# ReboostV2__Isense.net
KiCad netlist of a schematic drawn in Altium Designer
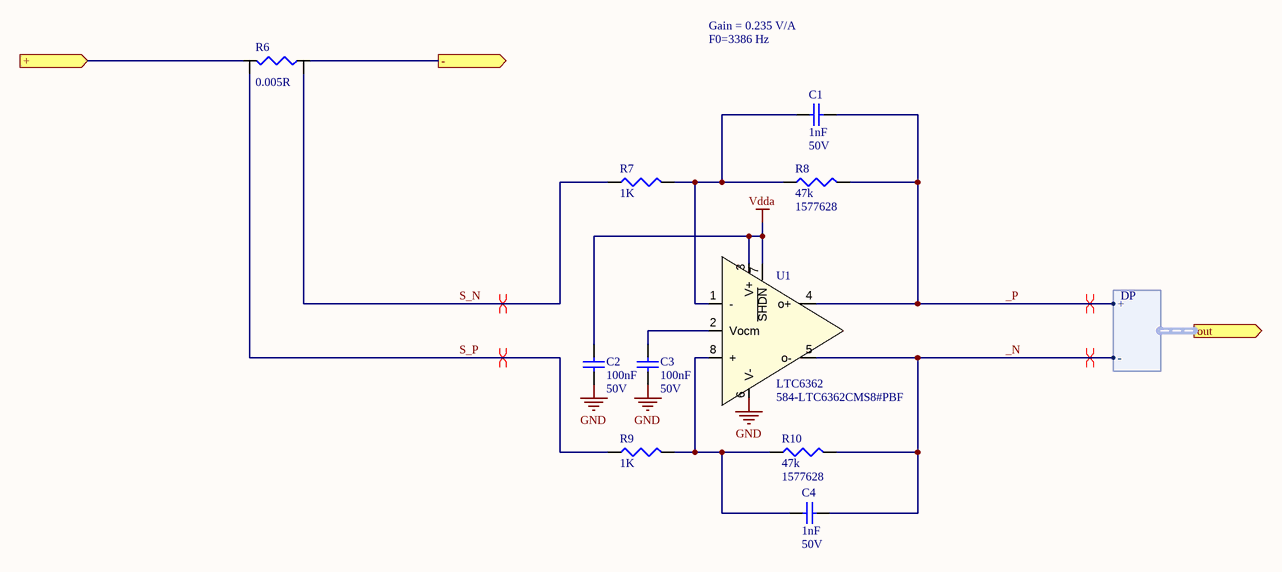
[diagram p0: ReboostV2__Isense.SchDoc]

(export (version "E")
  (design (tool "Eeschema 10.0.6"))
  (components
    (comp (ref "C1")
      (value "1nF")
      (footprint "C0603")
      (description "Capacitor, 1nF, 50V, X7R")
      (fields
        (field (name "VOLTAGE RATING") "50V")
        (field (name "MANUFACTURER") "KEMET")
        (field (name "MANUFACTURER PART NUMBER") "C0603C102K5RACTU")
      )
      (libsource (lib "Reboostv2") (part "1nF/0603/CER/50V"))
    )
    (comp (ref "C2")
      (value "100nF")
      (footprint "C0603")
      (description "Capacitor, 100nF, 50V, X7R")
      (fields
        (field (name "VOLTAGE RATING") "50V")
        (field (name "MANUFACTURER") "MULTICOMP")
        (field (name "MANUFACTURER PART NUMBER") "MCCA000255")
      )
      (libsource (lib "Reboostv2") (part "100nF/0603/CER/50V"))
    )
    (comp (ref "C3")
      (value "100nF")
      (footprint "C0603")
      (description "Capacitor, 100nF, 50V, X7R")
      (fields
        (field (name "VOLTAGE RATING") "50V")
        (field (name "MANUFACTURER") "MULTICOMP")
        (field (name "MANUFACTURER PART NUMBER") "MCCA000255")
      )
      (libsource (lib "Reboostv2") (part "100nF/0603/CER/50V"))
    )
    (comp (ref "C4")
      (value "1nF")
      (footprint "C0603")
      (description "Capacitor, 1nF, 50V, X7R")
      (fields
        (field (name "VOLTAGE RATING") "50V")
        (field (name "MANUFACTURER") "KEMET")
        (field (name "MANUFACTURER PART NUMBER") "C0603C102K5RACTU")
      )
      (libsource (lib "Reboostv2") (part "1nF/0603/CER/50V"))
    )
    (comp (ref "R6")
      (value "0.005R")
      (footprint "2512-L-4T")
      (description "Resistor, 0.005R, 1%, 2W, 50PPM")
      (fields
        (field (name "MANUFACTURER") "OHMITE")
        (field (name "MANUFACTURER PART NUMBER") "FC4L64R005FER")
      )
      (libsource (lib "Reboostv2") (part "0.005/2512/2000W/200V"))
    )
    (comp (ref "R7")
      (value "1K")
      (footprint "0603")
      (description "Resistor, 1K, 1%, 0.063W, 50V, 100PPM, 0603")
      (fields
        (field (name "MANUFACTURER") "VISHAY DRALORIC")
        (field (name "MANUFACTURER PART NUMBER") "CRCW06031K00FKEA")
      )
      (libsource (lib "Reboostv2") (part "1K/0603/0063W/50V"))
    )
    (comp (ref "R8")
      (value "47k")
      (footprint "0603")
      (description "Resistor, 47K, 0.1%, 0.063W, 50V, 100PPM, 0603")
      (fields
        (field (name "SUPPLIER PART NUMBER 1") "1577628")
        (field (name "MANUFACTURER") "PANASONIC")
        (field (name "MANUFACTURER PART NUMBER") "ERA3AEB473V")
      )
      (libsource (lib "Reboostv2") (part "47K/0603/0063W/50V_1"))
    )
    (comp (ref "R9")
      (value "1K")
      (footprint "0603")
      (description "Resistor, 1K, 1%, 0.063W, 50V, 100PPM, 0603")
      (fields
        (field (name "MANUFACTURER") "VISHAY DRALORIC")
        (field (name "MANUFACTURER PART NUMBER") "CRCW06031K00FKEA")
      )
      (libsource (lib "Reboostv2") (part "1K/0603/0063W/50V"))
    )
    (comp (ref "R10")
      (value "47k")
      (footprint "0603")
      (description "Resistor, 47K, 0.1%, 0.063W, 50V, 100PPM, 0603")
      (fields
        (field (name "SUPPLIER PART NUMBER 1") "1577628")
        (field (name "MANUFACTURER") "PANASONIC")
        (field (name "MANUFACTURER PART NUMBER") "ERA3AEB473V")
      )
      (libsource (lib "Reboostv2") (part "47K/0603/0063W/50V_1"))
    )
    (comp (ref "U1")
      (value "LTC6362")
      (footprint "MSOP8")
      (description "Precision, Low Power Rail-to-Rail Input/Output Differential Op Amp")
      (fields
        (field (name "SUPPLIER PART NUMBER 1") "584-LTC6362CMS8#PBF")
        (field (name "MANUFACTURER") "Analog Devices Inc.")
        (field (name "MANUFACTURER PART NUMBER") "LTC6362HMS8#PBF")
      )
      (libsource (lib "Reboostv2") (part "LTC6362HMS8"))
    )
  )
  (nets
    (net (code "2") (name "/+") (class "Default")
      (node (ref "R6") (pin "1") (pinfunction "1_1") (pintype "passive"))
    )
    (net (code "3") (name "/-") (class "Default")
      (node (ref "R6") (pin "2") (pinfunction "2_2") (pintype "passive"))
    )
    (net (code "4") (name "/S_N") (class "Default")
      (node (ref "R6") (pin "4") (pinfunction "4_4") (pintype "passive"))
      (node (ref "R7") (pin "1") (pinfunction "1_1") (pintype "passive"))
    )
    (net (code "5") (name "/S_P") (class "Default")
      (node (ref "R6") (pin "3") (pinfunction "3_3") (pintype "passive"))
      (node (ref "R9") (pin "1") (pinfunction "1_1") (pintype "passive"))
    )
    (net (code "6") (name "/_N") (class "Default")
      (node (ref "C4") (pin "2") (pinfunction "2_2") (pintype "passive"))
      (node (ref "R10") (pin "2") (pinfunction "2_2") (pintype "passive"))
      (node (ref "U1") (pin "5") (pinfunction "o-_5") (pintype "passive"))
    )
    (net (code "7") (name "/_P") (class "Default")
      (node (ref "C1") (pin "2") (pinfunction "2_2") (pintype "passive"))
      (node (ref "R8") (pin "2") (pinfunction "2_2") (pintype "passive"))
      (node (ref "U1") (pin "4") (pinfunction "o+_4") (pintype "passive"))
    )
    (net (code "9") (name "GND") (class "Default")
      (node (ref "C2") (pin "1") (pinfunction "1_1") (pintype "passive"))
      (node (ref "C3") (pin "1") (pinfunction "1_1") (pintype "passive"))
      (node (ref "U1") (pin "6") (pinfunction "V-_6") (pintype "passive"))
    )
    (net (code "10") (name "Net-(U1-+)") (class "Default")
      (node (ref "C4") (pin "1") (pinfunction "1_1") (pintype "passive"))
      (node (ref "R10") (pin "1") (pinfunction "1_1") (pintype "passive"))
      (node (ref "R9") (pin "2") (pinfunction "2_2") (pintype "passive"))
      (node (ref "U1") (pin "8") (pinfunction "+_8") (pintype "passive"))
    )
    (net (code "11") (name "Net-(U1--)") (class "Default")
      (node (ref "C1") (pin "1") (pinfunction "1_1") (pintype "passive"))
      (node (ref "R7") (pin "2") (pinfunction "2_2") (pintype "passive"))
      (node (ref "R8") (pin "1") (pinfunction "1_1") (pintype "passive"))
      (node (ref "U1") (pin "1") (pinfunction "-_1") (pintype "passive"))
    )
    (net (code "12") (name "Net-(U1-Vocm)") (class "Default")
      (node (ref "C3") (pin "2") (pinfunction "2_2") (pintype "passive"))
      (node (ref "U1") (pin "2") (pinfunction "Vocm_2") (pintype "passive"))
    )
    (net (code "13") (name "Vdda") (class "Default")
      (node (ref "C2") (pin "2") (pinfunction "2_2") (pintype "passive"))
      (node (ref "U1") (pin "3") (pinfunction "V+_3") (pintype "passive"))
      (node (ref "U1") (pin "7") (pinfunction "~{SHDN}_7") (pintype "passive"))
    )
  )
)
